# CO2-Ampel-Pro_v12.net
KiCad netlist of a schematic drawn in EAGLE
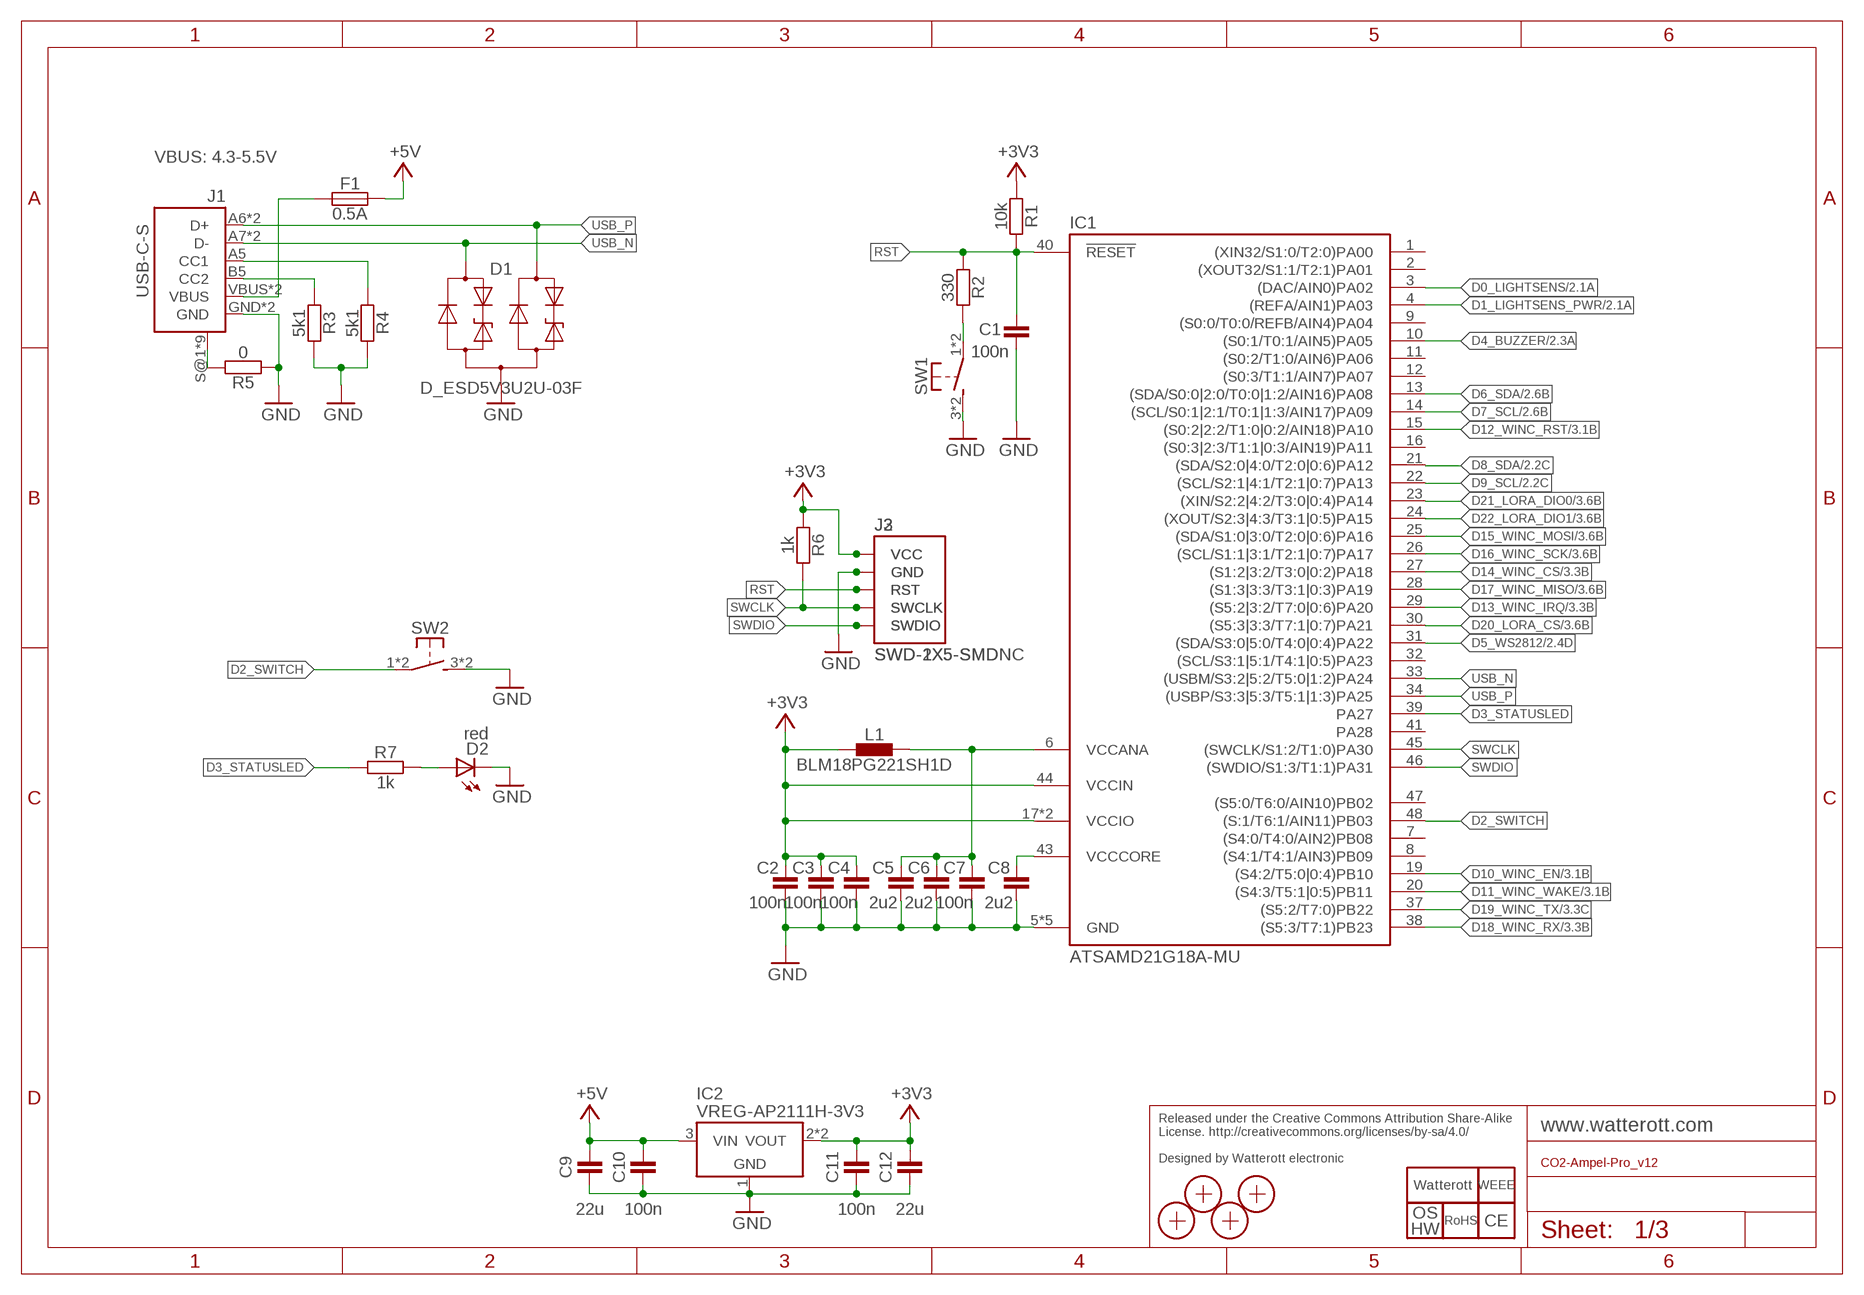
[diagram p0: schematic, sheet 1]
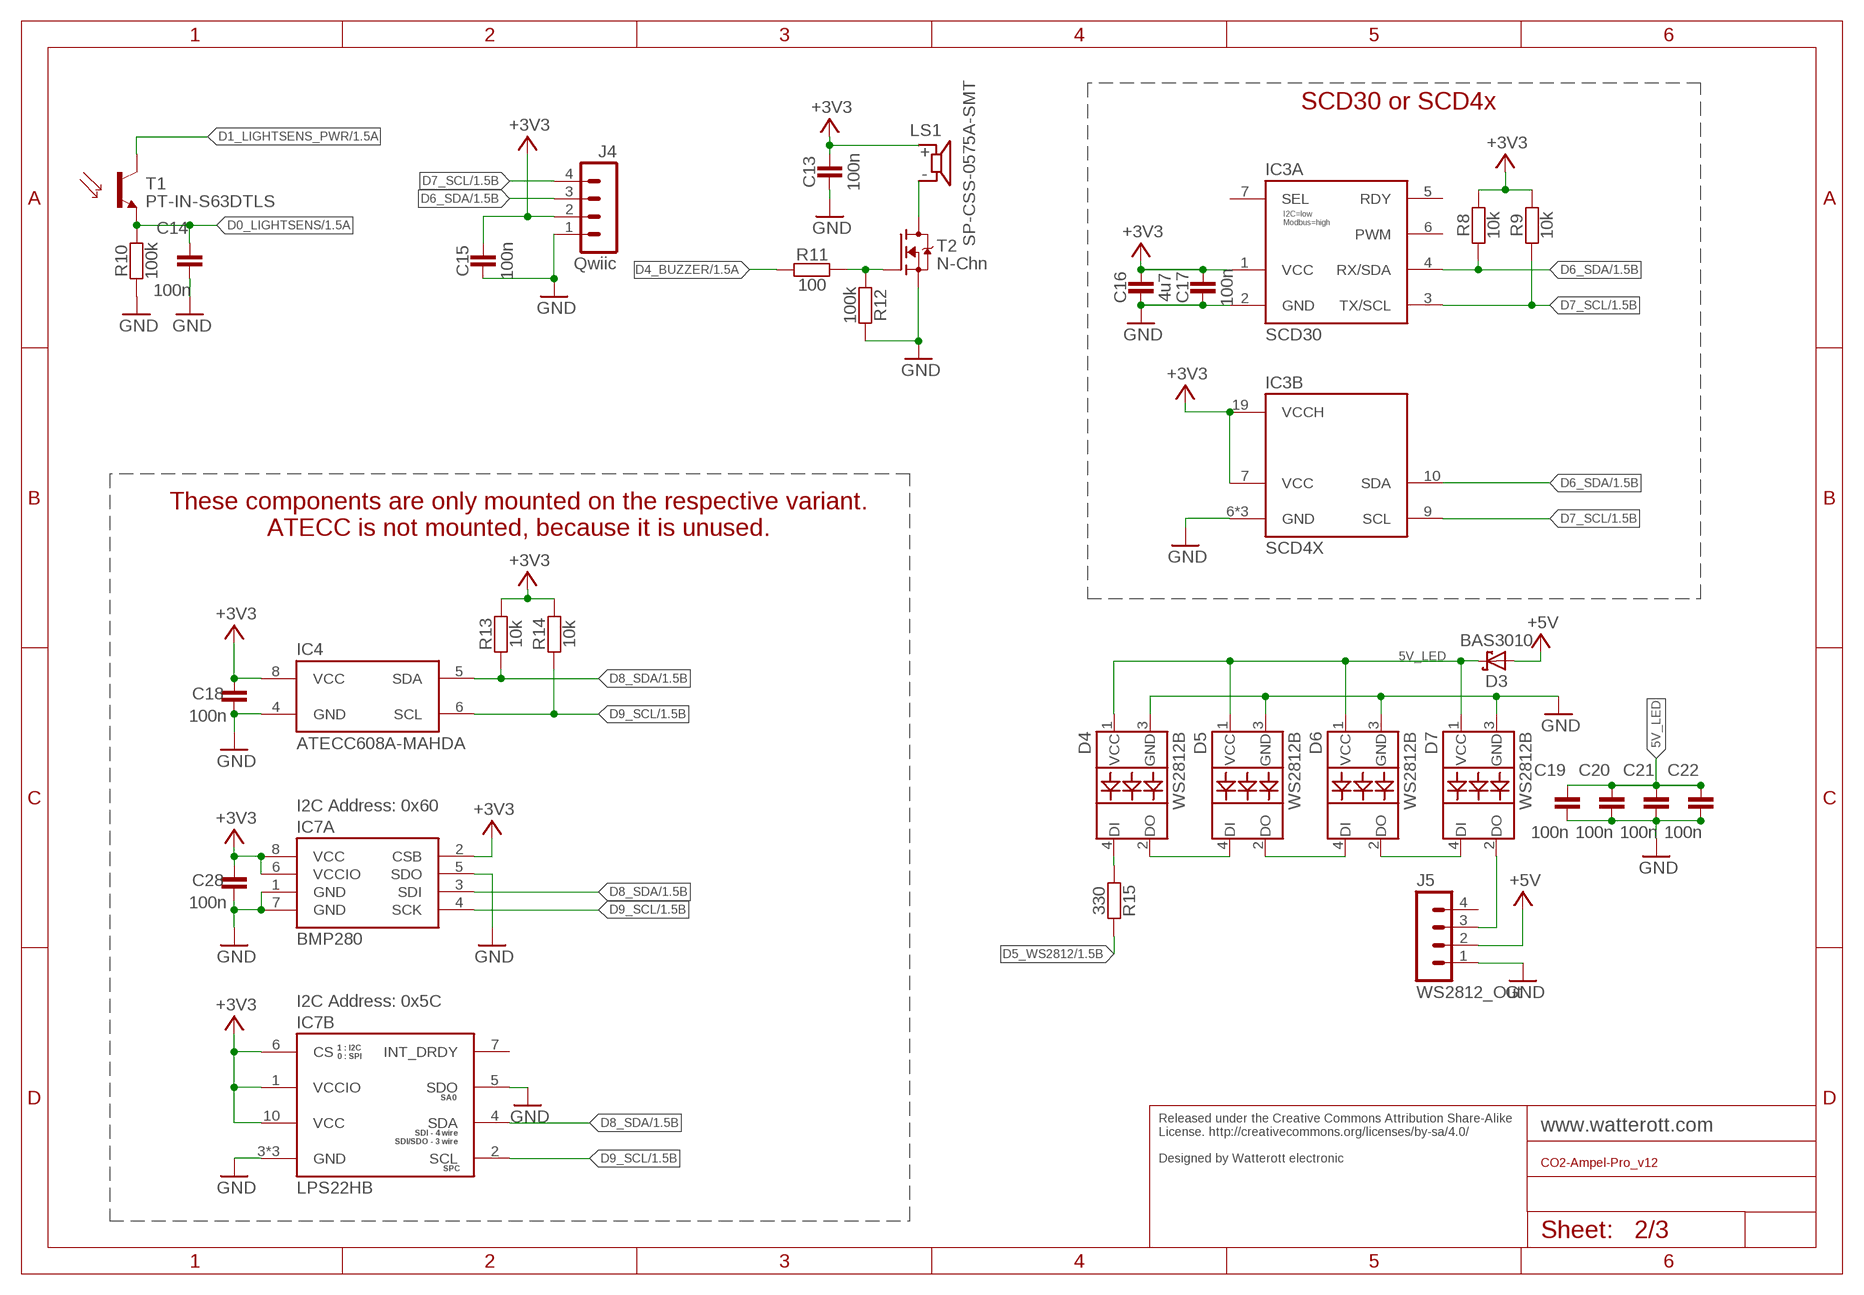
[diagram p1: schematic, sheet 2]
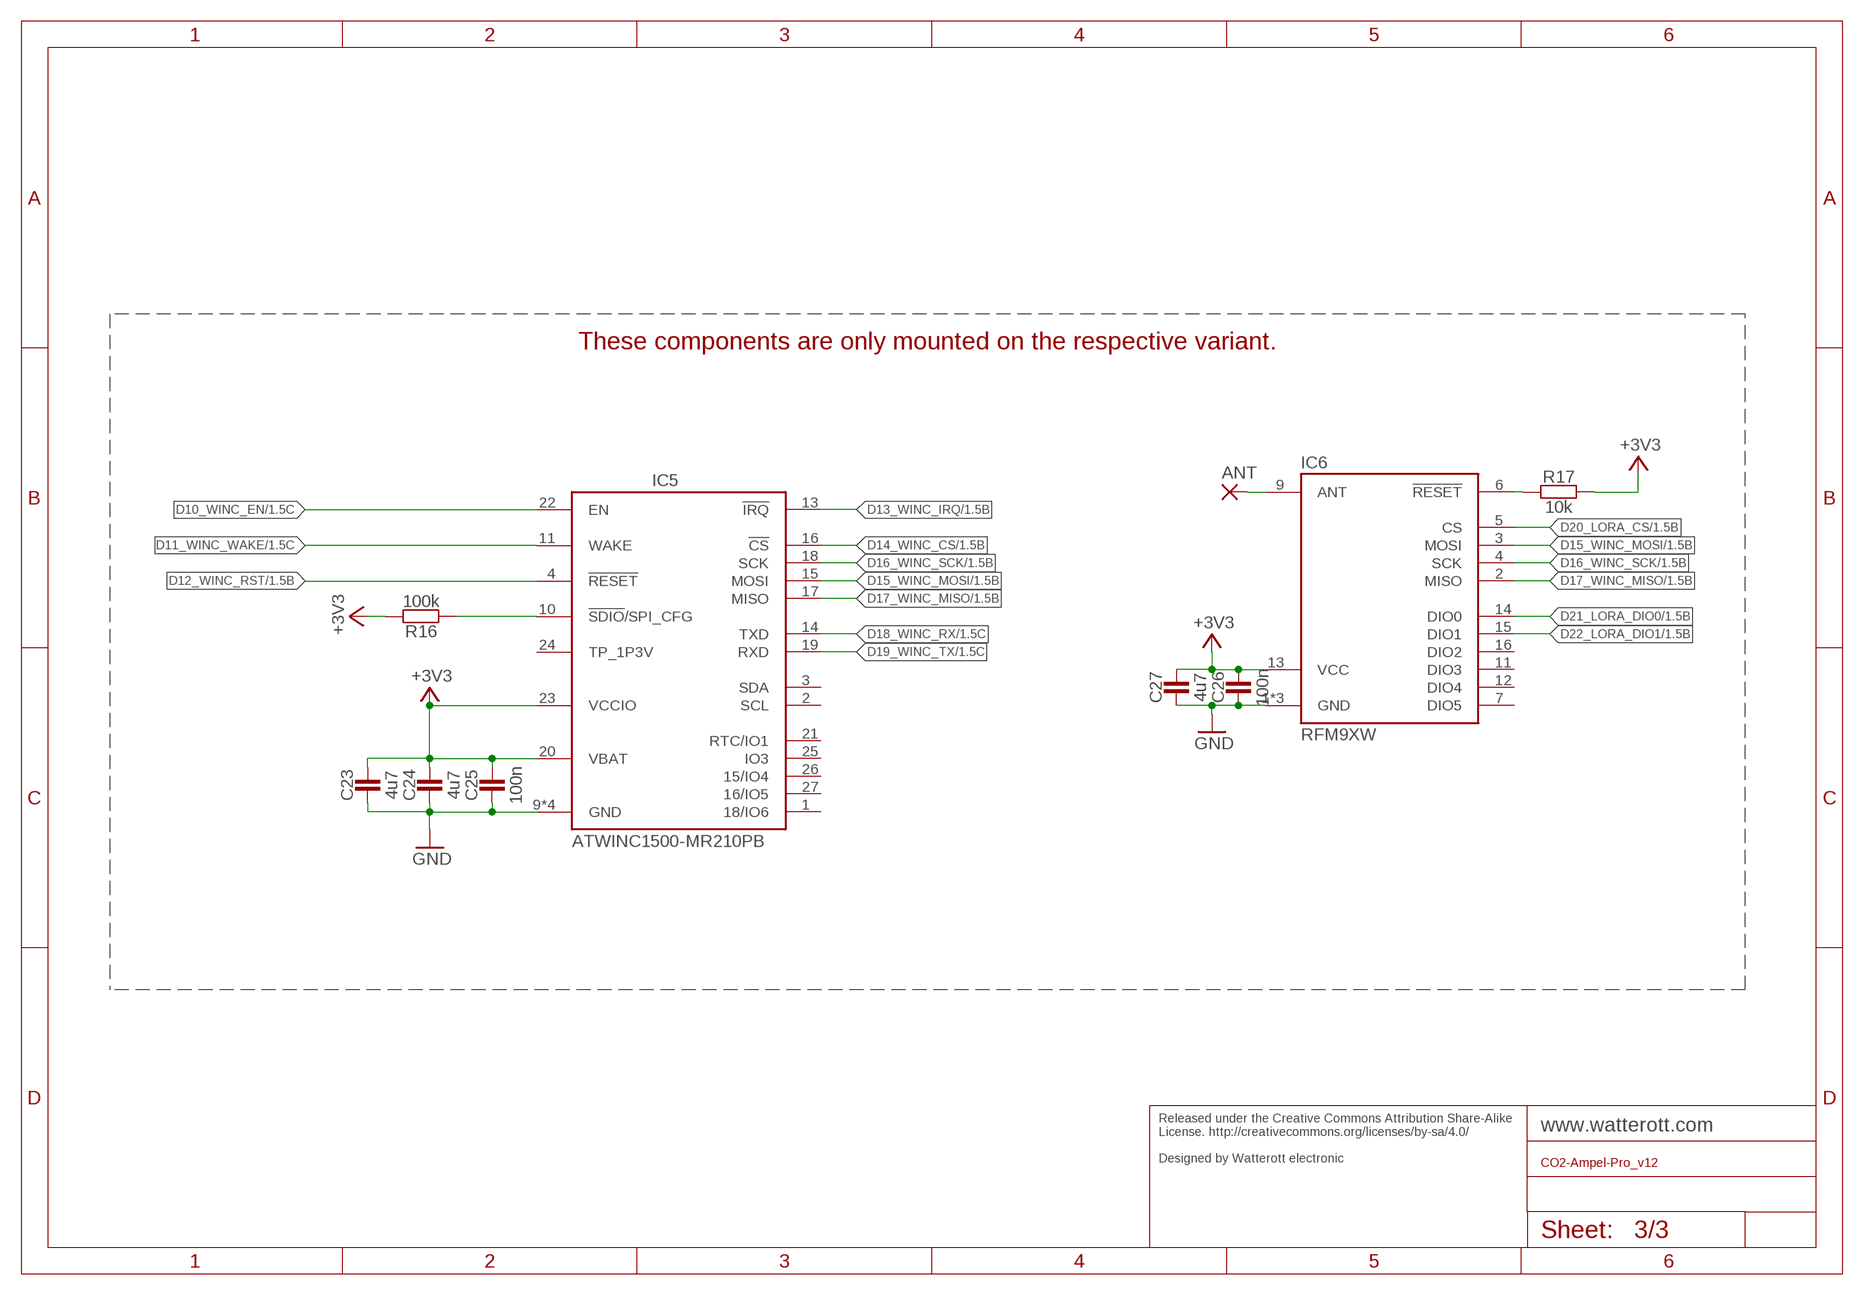
[diagram p2: schematic, sheet 3]

(export (version "E")
  (design (tool "Eeschema 10.0.6"))
  (components
    (comp (ref "C13")
      (value "100n")
      (footprint "eagle-import:C0402")
      (libsource (lib "eagle-import") (part "CAPACITOR-0402"))
    )
    (comp (ref "C14")
      (value "100n")
      (footprint "eagle-import:C0402")
      (libsource (lib "eagle-import") (part "CAPACITOR-0402"))
    )
    (comp (ref "C15")
      (value "100n")
      (footprint "eagle-import:C0402")
      (libsource (lib "eagle-import") (part "CAPACITOR-0402"))
    )
    (comp (ref "C16")
      (value "4u7")
      (footprint "eagle-import:C0402")
      (libsource (lib "eagle-import") (part "CAPACITOR-0402"))
    )
    (comp (ref "C17")
      (value "100n")
      (footprint "eagle-import:C0402")
      (libsource (lib "eagle-import") (part "CAPACITOR-0402"))
    )
    (comp (ref "C18")
      (value "100n")
      (footprint "eagle-import:C0402")
      (libsource (lib "eagle-import") (part "CAPACITOR-0402"))
    )
    (comp (ref "C19")
      (value "100n")
      (footprint "eagle-import:C0402")
      (libsource (lib "eagle-import") (part "CAPACITOR-0402"))
    )
    (comp (ref "C20")
      (value "100n")
      (footprint "eagle-import:C0402")
      (libsource (lib "eagle-import") (part "CAPACITOR-0402"))
    )
    (comp (ref "C21")
      (value "100n")
      (footprint "eagle-import:C0402")
      (libsource (lib "eagle-import") (part "CAPACITOR-0402"))
    )
    (comp (ref "C22")
      (value "100n")
      (footprint "eagle-import:C0402")
      (libsource (lib "eagle-import") (part "CAPACITOR-0402"))
    )
    (comp (ref "C28")
      (value "100n")
      (footprint "eagle-import:C0402")
      (libsource (lib "eagle-import") (part "CAPACITOR-0402"))
    )
    (comp (ref "D3")
      (value "BAS3010")
      (footprint "eagle-import:SOD323")
      (libsource (lib "eagle-import") (part "D_SCHOTTKY-SOD323"))
    )
    (comp (ref "D4")
      (value "WS2812B")
      (footprint "eagle-import:WS2812B")
      (libsource (lib "eagle-import") (part "WS2812B"))
    )
    (comp (ref "D5")
      (value "WS2812B")
      (footprint "eagle-import:WS2812B")
      (libsource (lib "eagle-import") (part "WS2812B"))
    )
    (comp (ref "D6")
      (value "WS2812B")
      (footprint "eagle-import:WS2812B")
      (libsource (lib "eagle-import") (part "WS2812B"))
    )
    (comp (ref "D7")
      (value "WS2812B")
      (footprint "eagle-import:WS2812B")
      (libsource (lib "eagle-import") (part "WS2812B"))
    )
    (comp (ref "IC3A")
      (value "SCD30")
      (footprint "eagle-import:SCD30")
      (libsource (lib "eagle-import") (part "SCD30"))
    )
    (comp (ref "IC3B")
      (value "SCD4X")
      (footprint "eagle-import:SCD4X")
      (libsource (lib "eagle-import") (part "SCD4X"))
    )
    (comp (ref "IC4")
      (value "ATECC608A-MAHDA")
      (footprint "eagle-import:UDFN8")
      (libsource (lib "eagle-import") (part "ATECC608A-MAHDA"))
    )
    (comp (ref "IC7A")
      (value "BMP280")
      (footprint "eagle-import:LGA8")
      (libsource (lib "eagle-import") (part "BMP280"))
    )
    (comp (ref "IC7B")
      (value "LPS22HB")
      (footprint "eagle-import:LPS22HB")
      (libsource (lib "eagle-import") (part "LPS22HB"))
    )
    (comp (ref "J4")
      (value "Qwiic")
      (footprint "eagle-import:JST_SM04B-SRSS-TB")
      (libsource (lib "eagle-import") (part "JST4-SM04B-SRSS-TB"))
    )
    (comp (ref "J5")
      (value "WS2812_Out")
      (footprint "eagle-import:JST_SM04B-SRSS-TB")
      (libsource (lib "eagle-import") (part "JST4-SM04B-SRSS-TB"))
    )
    (comp (ref "LS1")
      (value "SP-CSS-0575A-SMT")
      (footprint "eagle-import:CUI_CSS-0575A-SMT")
      (fields (field (name "MF") "CUI") (field (name "MPN") "CSS-0575A-SMT"))
      (libsource (lib "eagle-import") (part "SP-CSS-0575A-SMT"))
    )
    (comp (ref "R8")
      (value "10k")
      (footprint "eagle-import:C0402")
      (libsource (lib "eagle-import") (part "RESISTOR-0402"))
    )
    (comp (ref "R9")
      (value "10k")
      (footprint "eagle-import:C0402")
      (libsource (lib "eagle-import") (part "RESISTOR-0402"))
    )
    (comp (ref "R10")
      (value "100k")
      (footprint "eagle-import:C0402")
      (libsource (lib "eagle-import") (part "RESISTOR-0402"))
    )
    (comp (ref "R11")
      (value "100")
      (footprint "eagle-import:C0402")
      (libsource (lib "eagle-import") (part "RESISTOR-0402"))
    )
    (comp (ref "R12")
      (value "100k")
      (footprint "eagle-import:C0402")
      (libsource (lib "eagle-import") (part "RESISTOR-0402"))
    )
    (comp (ref "R13")
      (value "10k")
      (footprint "eagle-import:C0402")
      (libsource (lib "eagle-import") (part "RESISTOR-0402"))
    )
    (comp (ref "R14")
      (value "10k")
      (footprint "eagle-import:C0402")
      (libsource (lib "eagle-import") (part "RESISTOR-0402"))
    )
    (comp (ref "R15")
      (value "330")
      (footprint "eagle-import:C0402")
      (libsource (lib "eagle-import") (part "RESISTOR-0402"))
    )
    (comp (ref "T1")
      (value "PT-IN-S63DTLS")
      (footprint "eagle-import:C0603T")
      (libsource (lib "eagle-import") (part "PT-IN-S63DTLS"))
    )
    (comp (ref "T2")
      (value "N-Chn")
      (footprint "eagle-import:SOT23")
      (libsource (lib "eagle-import") (part "MOSFET-N-SOT23"))
    )
    (comp (ref "C1")
      (value "100n")
      (footprint "eagle-import:C0402")
      (libsource (lib "eagle-import") (part "CAPACITOR-0402"))
    )
    (comp (ref "C2")
      (value "100n")
      (footprint "eagle-import:C0402")
      (libsource (lib "eagle-import") (part "CAPACITOR-0402"))
    )
    (comp (ref "C3")
      (value "100n")
      (footprint "eagle-import:C0402")
      (libsource (lib "eagle-import") (part "CAPACITOR-0402"))
    )
    (comp (ref "C4")
      (value "100n")
      (footprint "eagle-import:C0402")
      (libsource (lib "eagle-import") (part "CAPACITOR-0402"))
    )
    (comp (ref "C5")
      (value "2u2")
      (footprint "eagle-import:C0402")
      (libsource (lib "eagle-import") (part "CAPACITOR-0402"))
    )
    (comp (ref "C6")
      (value "2u2")
      (footprint "eagle-import:C0402")
      (libsource (lib "eagle-import") (part "CAPACITOR-0402"))
    )
    (comp (ref "C7")
      (value "100n")
      (footprint "eagle-import:C0402")
      (libsource (lib "eagle-import") (part "CAPACITOR-0402"))
    )
    (comp (ref "C8")
      (value "2u2")
      (footprint "eagle-import:C0402")
      (libsource (lib "eagle-import") (part "CAPACITOR-0402"))
    )
    (comp (ref "C9")
      (value "22u")
      (footprint "eagle-import:C0805")
      (libsource (lib "eagle-import") (part "CAPACITOR-0805"))
    )
    (comp (ref "C10")
      (value "100n")
      (footprint "eagle-import:C0402")
      (libsource (lib "eagle-import") (part "CAPACITOR-0402"))
    )
    (comp (ref "C11")
      (value "100n")
      (footprint "eagle-import:C0402")
      (libsource (lib "eagle-import") (part "CAPACITOR-0402"))
    )
    (comp (ref "C12")
      (value "22u")
      (footprint "eagle-import:C0805")
      (libsource (lib "eagle-import") (part "CAPACITOR-0805"))
    )
    (comp (ref "D1")
      (value "D_ESD5V3U2U-03F")
      (footprint "eagle-import:SOT723")
      (libsource (lib "eagle-import") (part "D_ESD5V3U2U-03F"))
    )
    (comp (ref "D2")
      (value "red")
      (footprint "eagle-import:C0603")
      (libsource (lib "eagle-import") (part "LED-0603"))
    )
    (comp (ref "F1")
      (value "0.5A")
      (footprint "eagle-import:C0805")
      (libsource (lib "eagle-import") (part "FUSE-0805"))
    )
    (comp (ref "IC1")
      (value "ATSAMD21G18A-MU")
      (footprint "eagle-import:QFN48-PAD")
      (libsource (lib "eagle-import") (part "ATSAMD21G18A-MU"))
    )
    (comp (ref "IC2")
      (value "VREG-AP2111H-3V3")
      (footprint "eagle-import:SOT223")
      (libsource (lib "eagle-import") (part "VREG-TS1117CW-3V3"))
    )
    (comp (ref "J1")
      (value "USB-C-S")
      (footprint "eagle-import:USB-C-S")
      (libsource (lib "eagle-import") (part "USB-C-S"))
    )
    (comp (ref "J2")
      (value "SWD-2X5-SMD")
      (footprint "eagle-import:SWD-2X5_SMD")
      (libsource (lib "eagle-import") (part "SWD-2X5-SMD"))
    )
    (comp (ref "J3")
      (value "SWD-1X5-SMDNC")
      (footprint "eagle-import:SWD-1X5_SMDNC")
      (libsource (lib "eagle-import") (part "SWD-1X5-SMDNC"))
    )
    (comp (ref "L1")
      (value "BLM18PG221SH1D")
      (footprint "eagle-import:C0603")
      (libsource (lib "eagle-import") (part "INDUCTOR-0603"))
    )
    (comp (ref "LOGO1")
      (value "LOGO_SPARK-4")
      (footprint "eagle-import:SPARK_4MM")
      (libsource (lib "eagle-import") (part "LOGO_SPARK-4"))
    )
    (comp (ref "LOGO2")
      (value "LOGO_WEEE-4")
      (footprint "eagle-import:WEEE_4MM")
      (libsource (lib "eagle-import") (part "LOGO_WEEE-4"))
    )
    (comp (ref "LOGO3")
      (value "OSHW_LOGOX0070")
      (footprint "eagle-import:OSHW_3MM")
      (libsource (lib "eagle-import") (part "LOGO_OSHW-3"))
    )
    (comp (ref "LOGO4")
      (value "LOGO_ROHS-4")
      (footprint "eagle-import:ROHS_4MM")
      (libsource (lib "eagle-import") (part "LOGO_ROHS-4"))
    )
    (comp (ref "LOGO5")
      (value "LOGO_CE-4")
      (footprint "eagle-import:CE_4MM")
      (libsource (lib "eagle-import") (part "LOGO_CE-4"))
    )
    (comp (ref "R1")
      (value "10k")
      (footprint "eagle-import:C0402")
      (libsource (lib "eagle-import") (part "RESISTOR-0402"))
    )
    (comp (ref "R2")
      (value "330")
      (footprint "eagle-import:C0402")
      (libsource (lib "eagle-import") (part "RESISTOR-0402"))
    )
    (comp (ref "R3")
      (value "5k1")
      (footprint "eagle-import:C0402")
      (libsource (lib "eagle-import") (part "RESISTOR-0402"))
    )
    (comp (ref "R4")
      (value "5k1")
      (footprint "eagle-import:C0402")
      (libsource (lib "eagle-import") (part "RESISTOR-0402"))
    )
    (comp (ref "R5")
      (value "0")
      (footprint "eagle-import:C0603")
      (libsource (lib "eagle-import") (part "RESISTOR-0603"))
    )
    (comp (ref "R6")
      (value "1k")
      (footprint "eagle-import:C0402")
      (libsource (lib "eagle-import") (part "RESISTOR-0402"))
    )
    (comp (ref "R7")
      (value "1k")
      (footprint "eagle-import:C0402")
      (libsource (lib "eagle-import") (part "RESISTOR-0402"))
    )
    (comp (ref "SW1")
      (value "PTS645SK50SMTR92-Red")
      (footprint "eagle-import:PTS840P")
      (libsource (lib "eagle-import") (part "SW-TACTILE-PTS840P"))
    )
    (comp (ref "SW2")
      (value "PTS645SH50SMTR92-Grey")
      (footprint "eagle-import:PTS840P")
      (libsource (lib "eagle-import") (part "SW-TACTILE-PTS840P"))
    )
    (comp (ref "X1")
      (value "PASSER-07")
      (footprint "eagle-import:PASSER_07MM")
      (libsource (lib "eagle-import") (part "PASSER-07"))
    )
    (comp (ref "X2")
      (value "PASSER-07")
      (footprint "eagle-import:PASSER_07MM")
      (libsource (lib "eagle-import") (part "PASSER-07"))
    )
    (comp (ref "X3")
      (value "PASSER-07")
      (footprint "eagle-import:PASSER_07MM")
      (libsource (lib "eagle-import") (part "PASSER-07"))
    )
    (comp (ref "X4")
      (value "PASSER-07")
      (footprint "eagle-import:PASSER_07MM")
      (libsource (lib "eagle-import") (part "PASSER-07"))
    )
    (comp (ref "ANT")
      (value "1,6/0,9")
      (footprint "eagle-import:1,6_0,9")
      (libsource (lib "eagle-import") (part "1,6/0,9"))
    )
    (comp (ref "C23")
      (value "4u7")
      (footprint "eagle-import:C0402")
      (libsource (lib "eagle-import") (part "CAPACITOR-0402"))
    )
    (comp (ref "C24")
      (value "4u7")
      (footprint "eagle-import:C0402")
      (libsource (lib "eagle-import") (part "CAPACITOR-0402"))
    )
    (comp (ref "C25")
      (value "100n")
      (footprint "eagle-import:C0402")
      (libsource (lib "eagle-import") (part "CAPACITOR-0402"))
    )
    (comp (ref "C26")
      (value "100n")
      (footprint "eagle-import:C0402")
      (libsource (lib "eagle-import") (part "CAPACITOR-0402"))
    )
    (comp (ref "C27")
      (value "4u7")
      (footprint "eagle-import:C0402")
      (libsource (lib "eagle-import") (part "CAPACITOR-0402"))
    )
    (comp (ref "IC5")
      (value "ATWINC1500-MR210PB")
      (footprint "eagle-import:ATWINC1500-MX210")
      (libsource (lib "eagle-import") (part "ATWINC1500-MR210PB"))
    )
    (comp (ref "IC6")
      (value "RFM9XW")
      (footprint "eagle-import:RFM9X")
      (libsource (lib "eagle-import") (part "RFM9XW"))
    )
    (comp (ref "R16")
      (value "100k")
      (footprint "eagle-import:C0402")
      (libsource (lib "eagle-import") (part "RESISTOR-0402"))
    )
    (comp (ref "R17")
      (value "10k")
      (footprint "eagle-import:C0402")
      (libsource (lib "eagle-import") (part "RESISTOR-0402"))
    )
  )
  (nets
    (net (code "1") (name "+3V3") (class "Default")
      (node (ref "C11") (pin "2") (pinfunction "2_2") (pintype "passive"))
      (node (ref "C12") (pin "2") (pinfunction "2_2") (pintype "passive"))
      (node (ref "C13") (pin "2") (pinfunction "2_2") (pintype "passive"))
      (node (ref "C15") (pin "2") (pinfunction "2_2") (pintype "passive"))
      (node (ref "C16") (pin "2") (pinfunction "2_2") (pintype "passive"))
      (node (ref "C17") (pin "2") (pinfunction "2_2") (pintype "passive"))
      (node (ref "C18") (pin "2") (pinfunction "2_2") (pintype "passive"))
      (node (ref "C2") (pin "2") (pinfunction "2_2") (pintype "passive"))
      (node (ref "C23") (pin "2") (pinfunction "2_2") (pintype "passive"))
      (node (ref "C24") (pin "2") (pinfunction "2_2") (pintype "passive"))
      (node (ref "C25") (pin "2") (pinfunction "2_2") (pintype "passive"))
      (node (ref "C26") (pin "2") (pinfunction "2_2") (pintype "passive"))
      (node (ref "C27") (pin "2") (pinfunction "2_2") (pintype "passive"))
      (node (ref "C28") (pin "2") (pinfunction "2_2") (pintype "passive"))
      (node (ref "C3") (pin "2") (pinfunction "2_2") (pintype "passive"))
      (node (ref "C4") (pin "2") (pinfunction "2_2") (pintype "passive"))
      (node (ref "IC1") (pin "17") (pinfunction "VCCIO_17") (pintype "power_in"))
      (node (ref "IC1") (pin "36") (pinfunction "VCCIO_36") (pintype "power_in"))
      (node (ref "IC1") (pin "44") (pinfunction "VCCIN_44") (pintype "power_in"))
      (node (ref "IC2") (pin "2") (pinfunction "VOUT_2") (pintype "power_in"))
      (node (ref "IC2") (pin "4") (pinfunction "VOUT_4") (pintype "power_in"))
      (node (ref "IC3A") (pin "1") (pinfunction "VCC_1") (pintype "power_in"))
      (node (ref "IC3B") (pin "19") (pinfunction "VCCH_19") (pintype "bidirectional"))
      (node (ref "IC3B") (pin "7") (pinfunction "VCC_7") (pintype "power_in"))
      (node (ref "IC4") (pin "8") (pinfunction "VCC_8") (pintype "power_in"))
      (node (ref "IC5") (pin "20") (pinfunction "VBAT_20") (pintype "power_in"))
      (node (ref "IC5") (pin "23") (pinfunction "VCCIO_23") (pintype "power_in"))
      (node (ref "IC6") (pin "13") (pinfunction "VCC_13") (pintype "power_in"))
      (node (ref "IC7A") (pin "2") (pinfunction "CSB_2") (pintype "input"))
      (node (ref "IC7A") (pin "6") (pinfunction "VCCIO_6") (pintype "power_in"))
      (node (ref "IC7A") (pin "8") (pinfunction "VCC_8") (pintype "power_in"))
      (node (ref "IC7B") (pin "1") (pinfunction "VCCIO_1") (pintype "bidirectional"))
      (node (ref "IC7B") (pin "10") (pinfunction "VCC_10") (pintype "power_in"))
      (node (ref "IC7B") (pin "6") (pinfunction "CS_6") (pintype "bidirectional"))
      (node (ref "J2") (pin "VCC") (pinfunction "VCC_VCC") (pintype "power_in"))
      (node (ref "J3") (pin "1-VCC") (pinfunction "VCC_1-VCC") (pintype "power_in"))
      (node (ref "J4") (pin "2") (pinfunction "2_2") (pintype "passive"))
      (node (ref "L1") (pin "1") (pinfunction "1_1") (pintype "passive"))
      (node (ref "LS1") (pin "+") (pinfunction "P_+") (pintype "passive"))
      (node (ref "R1") (pin "1") (pinfunction "1_1") (pintype "passive"))
      (node (ref "R13") (pin "2") (pinfunction "2_2") (pintype "passive"))
      (node (ref "R14") (pin "2") (pinfunction "2_2") (pintype "passive"))
      (node (ref "R16") (pin "2") (pinfunction "2_2") (pintype "passive"))
      (node (ref "R17") (pin "2") (pinfunction "2_2") (pintype "passive"))
      (node (ref "R6") (pin "1") (pinfunction "1_1") (pintype "passive"))
      (node (ref "R8") (pin "2") (pinfunction "2_2") (pintype "passive"))
      (node (ref "R9") (pin "2") (pinfunction "2_2") (pintype "passive"))
    )
    (net (code "2") (name "+5V") (class "Default")
      (node (ref "C10") (pin "2") (pinfunction "2_2") (pintype "passive"))
      (node (ref "C9") (pin "2") (pinfunction "2_2") (pintype "passive"))
      (node (ref "D3") (pin "A") (pinfunction "A_A") (pintype "passive"))
      (node (ref "F1") (pin "2") (pinfunction "2_2") (pintype "passive"))
      (node (ref "IC2") (pin "3") (pinfunction "VIN_3") (pintype "power_in"))
      (node (ref "J5") (pin "2") (pinfunction "2_2") (pintype "passive"))
    )
    (net (code "3") (name "5V_LED") (class "Default")
      (node (ref "C19") (pin "2") (pinfunction "2_2") (pintype "passive"))
      (node (ref "C20") (pin "2") (pinfunction "2_2") (pintype "passive"))
      (node (ref "C21") (pin "2") (pinfunction "2_2") (pintype "passive"))
      (node (ref "C22") (pin "2") (pinfunction "2_2") (pintype "passive"))
      (node (ref "D3") (pin "C") (pinfunction "C_C") (pintype "passive"))
      (node (ref "D4") (pin "1") (pinfunction "VCC_1") (pintype "power_in"))
      (node (ref "D5") (pin "1") (pinfunction "VCC_1") (pintype "power_in"))
      (node (ref "D6") (pin "1") (pinfunction "VCC_1") (pintype "power_in"))
      (node (ref "D7") (pin "1") (pinfunction "VCC_1") (pintype "power_in"))
    )
    (net (code "4") (name "D0_LIGHTSENS") (class "Default")
      (node (ref "C14") (pin "2") (pinfunction "2_2") (pintype "passive"))
      (node (ref "IC1") (pin "3") (pinfunction "(DAC/AIN0)PA02_3") (pintype "bidirectional"))
      (node (ref "R10") (pin "2") (pinfunction "2_2") (pintype "passive"))
      (node (ref "T1") (pin "E") (pinfunction "E_E") (pintype "passive"))
    )
    (net (code "5") (name "D1_LIGHTSENS_PWR") (class "Default")
      (node (ref "IC1") (pin "4") (pinfunction "(REFA/AIN1)PA03_4") (pintype "bidirectional"))
      (node (ref "T1") (pin "C") (pinfunction "C_C") (pintype "passive"))
    )
    (net (code "6") (name "D2_SWITCH") (class "Default")
      (node (ref "IC1") (pin "48") (pinfunction "(S:1/T6:1/AIN11)PB03_48") (pintype "bidirectional"))
      (node (ref "SW2") (pin "1") (pinfunction "P1_1") (pintype "passive"))
      (node (ref "SW2") (pin "2") (pinfunction "P1_2") (pintype "passive"))
    )
    (net (code "7") (name "D3_STATUSLED") (class "Default")
      (node (ref "IC1") (pin "39") (pinfunction "PA27_39") (pintype "bidirectional"))
      (node (ref "R7") (pin "1") (pinfunction "1_1") (pintype "passive"))
    )
    (net (code "8") (name "D4_BUZZER") (class "Default")
      (node (ref "IC1") (pin "10") (pinfunction "(S0:1/T0:1/AIN5)PA05_10") (pintype "bidirectional"))
      (node (ref "R11") (pin "1") (pinfunction "1_1") (pintype "passive"))
    )
    (net (code "9") (name "D5_WS2812") (class "Default")
      (node (ref "IC1") (pin "31") (pinfunction "(SDA/S3:0|5:0/T4:0|0:4)PA22_31") (pintype "bidirectional"))
      (node (ref "R15") (pin "2") (pinfunction "2_2") (pintype "passive"))
    )
    (net (code "10") (name "D6_SDA") (class "Default")
      (node (ref "IC1") (pin "13") (pinfunction "(SDA/S0:0|2:0/T0:0|1:2/AIN16)PA08_13") (pintype "bidirectional"))
      (node (ref "IC3A") (pin "4") (pinfunction "RX/SDA_4") (pintype "bidirectional"))
      (node (ref "IC3B") (pin "10") (pinfunction "SDA_10") (pintype "bidirectional"))
      (node (ref "J4") (pin "3") (pinfunction "3_3") (pintype "passive"))
      (node (ref "R8") (pin "1") (pinfunction "1_1") (pintype "passive"))
    )
    (net (code "11") (name "D7_SCL") (class "Default")
      (node (ref "IC1") (pin "14") (pinfunction "(SCL/S0:1|2:1/T0:1|1:3/AIN17)PA09_14") (pintype "bidirectional"))
      (node (ref "IC3A") (pin "3") (pinfunction "TX/SCL_3") (pintype "bidirectional"))
      (node (ref "IC3B") (pin "9") (pinfunction "SCL_9") (pintype "bidirectional"))
      (node (ref "J4") (pin "4") (pinfunction "4_4") (pintype "passive"))
      (node (ref "R9") (pin "1") (pinfunction "1_1") (pintype "passive"))
    )
    (net (code "12") (name "D8_SDA") (class "Default")
      (node (ref "IC1") (pin "21") (pinfunction "(SDA/S2:0|4:0/T2:0|0:6)PA12_21") (pintype "bidirectional"))
      (node (ref "IC4") (pin "5") (pinfunction "SDA_5") (pintype "bidirectional"))
      (node (ref "IC7A") (pin "3") (pinfunction "SDI_3") (pintype "bidirectional"))
      (node (ref "IC7B") (pin "4") (pinfunction "SDA_4") (pintype "bidirectional"))
      (node (ref "R13") (pin "1") (pinfunction "1_1") (pintype "passive"))
    )
    (net (code "13") (name "D9_SCL") (class "Default")
      (node (ref "IC1") (pin "22") (pinfunction "(SCL/S2:1|4:1/T2:1|0:7)PA13_22") (pintype "bidirectional"))
      (node (ref "IC4") (pin "6") (pinfunction "SCL_6") (pintype "bidirectional"))
      (node (ref "IC7A") (pin "4") (pinfunction "SCK_4") (pintype "bidirectional"))
      (node (ref "IC7B") (pin "2") (pinfunction "SCL_2") (pintype "bidirectional"))
      (node (ref "R14") (pin "1") (pinfunction "1_1") (pintype "passive"))
    )
    (net (code "14") (name "D10_WINC_EN") (class "Default")
      (node (ref "IC1") (pin "19") (pinfunction "(S4:2/T5:0|0:4)PB10_19") (pintype "bidirectional"))
      (node (ref "IC5") (pin "22") (pinfunction "EN_22") (pintype "input"))
    )
    (net (code "15") (name "D11_WINC_WAKE") (class "Default")
      (node (ref "IC1") (pin "20") (pinfunction "(S4:3/T5:1|0:5)PB11_20") (pintype "bidirectional"))
      (node (ref "IC5") (pin "11") (pinfunction "WAKE_11") (pintype "input"))
    )
    (net (code "16") (name "D12_WINC_RST") (class "Default")
      (node (ref "IC1") (pin "15") (pinfunction "(S0:2|2:2/T1:0|0:2/AIN18)PA10_15") (pintype "bidirectional"))
      (node (ref "IC5") (pin "4") (pinfunction "~{RESET}_4") (pintype "input"))
    )
    (net (code "17") (name "D13_WINC_IRQ") (class "Default")
      (node (ref "IC1") (pin "29") (pinfunction "(S5:2|3:2/T7:0|0:6)PA20_29") (pintype "bidirectional"))
      (node (ref "IC5") (pin "13") (pinfunction "~{IRQ}_13") (pintype "output"))
    )
    (net (code "18") (name "D14_WINC_CS") (class "Default")
      (node (ref "IC1") (pin "27") (pinfunction "(S1:2|3:2/T3:0|0:2)PA18_27") (pintype "bidirectional"))
      (node (ref "IC5") (pin "16") (pinfunction "~{CS}_16") (pintype "input"))
    )
    (net (code "19") (name "D15_WINC_MOSI") (class "Default")
      (node (ref "IC1") (pin "25") (pinfunction "(SDA/S1:0|3:0/T2:0|0:6)PA16_25") (pintype "bidirectional"))
      (node (ref "IC5") (pin "15") (pinfunction "MOSI_15") (pintype "input"))
      (node (ref "IC6") (pin "3") (pinfunction "MOSI_3") (pintype "input"))
    )
    (net (code "20") (name "D16_WINC_SCK") (class "Default")
      (node (ref "IC1") (pin "26") (pinfunction "(SCL/S1:1|3:1/T2:1|0:7)PA17_26") (pintype "bidirectional"))
      (node (ref "IC5") (pin "18") (pinfunction "SCK_18") (pintype "input"))
      (node (ref "IC6") (pin "4") (pinfunction "SCK_4") (pintype "input"))
    )
    (net (code "21") (name "D17_WINC_MISO") (class "Default")
      (node (ref "IC1") (pin "28") (pinfunction "(S1:3|3:3/T3:1|0:3)PA19_28") (pintype "bidirectional"))
      (node (ref "IC5") (pin "17") (pinfunction "MISO_17") (pintype "output"))
      (node (ref "IC6") (pin "2") (pinfunction "MISO_2") (pintype "output"))
    )
    (net (code "22") (name "D18_WINC_RX") (class "Default")
      (node (ref "IC1") (pin "38") (pinfunction "(S5:3/T7:1)PB23_38") (pintype "bidirectional"))
      (node (ref "IC5") (pin "14") (pinfunction "TXD_14") (pintype "output"))
    )
    (net (code "23") (name "D19_WINC_TX") (class "Default")
      (node (ref "IC1") (pin "37") (pinfunction "(S5:2/T7:0)PB22_37") (pintype "bidirectional"))
      (node (ref "IC5") (pin "19") (pinfunction "RXD_19") (pintype "input"))
    )
    (net (code "24") (name "D20_LORA_CS") (class "Default")
      (node (ref "IC1") (pin "30") (pinfunction "(S5:3|3:3/T7:1|0:7)PA21_30") (pintype "bidirectional"))
      (node (ref "IC6") (pin "5") (pinfunction "CS_5") (pintype "input"))
    )
    (net (code "25") (name "D21_LORA_DIO0") (class "Default")
      (node (ref "IC1") (pin "23") (pinfunction "(XIN/S2:2|4:2/T3:0|0:4)PA14_23") (pintype "bidirectional"))
      (node (ref "IC6") (pin "14") (pinfunction "DIO0_14") (pintype "bidirectional"))
    )
    (net (code "26") (name "D22_LORA_DIO1") (class "Default")
      (node (ref "IC1") (pin "24") (pinfunction "(XOUT/S2:3|4:3/T3:1|0:5)PA15_24") (pintype "bidirectional"))
      (node (ref "IC6") (pin "15") (pinfunction "DIO1_15") (pintype "bidirectional"))
    )
    (net (code "27") (name "GND") (class "Default")
      (node (ref "C1") (pin "1") (pinfunction "1_1") (pintype "passive"))
      (node (ref "C10") (pin "1") (pinfunction "1_1") (pintype "passive"))
      (node (ref "C11") (pin "1") (pinfunction "1_1") (pintype "passive"))
      (node (ref "C12") (pin "1") (pinfunction "1_1") (pintype "passive"))
      (node (ref "C13") (pin "1") (pinfunction "1_1") (pintype "passive"))
      (node (ref "C14") (pin "1") (pinfunction "1_1") (pintype "passive"))
      (node (ref "C15") (pin "1") (pinfunction "1_1") (pintype "passive"))
      (node (ref "C16") (pin "1") (pinfunction "1_1") (pintype "passive"))
      (node (ref "C17") (pin "1") (pinfunction "1_1") (pintype "passive"))
      (node (ref "C18") (pin "1") (pinfunction "1_1") (pintype "passive"))
      (node (ref "C19") (pin "1") (pinfunction "1_1") (pintype "passive"))
      (node (ref "C2") (pin "1") (pinfunction "1_1") (pintype "passive"))
      (node (ref "C20") (pin "1") (pinfunction "1_1") (pintype "passive"))
      (node (ref "C21") (pin "1") (pinfunction "1_1") (pintype "passive"))
      (node (ref "C22") (pin "1") (pinfunction "1_1") (pintype "passive"))
      (node (ref "C23") (pin "1") (pinfunction "1_1") (pintype "passive"))
      (node (ref "C24") (pin "1") (pinfunction "1_1") (pintype "passive"))
      (node (ref "C25") (pin "1") (pinfunction "1_1") (pintype "passive"))
      (node (ref "C26") (pin "1") (pinfunction "1_1") (pintype "passive"))
      (node (ref "C27") (pin "1") (pinfunction "1_1") (pintype "passive"))
      (node (ref "C28") (pin "1") (pinfunction "1_1") (pintype "passive"))
      (node (ref "C3") (pin "1") (pinfunction "1_1") (pintype "passive"))
      (node (ref "C4") (pin "1") (pinfunction "1_1") (pintype "passive"))
      (node (ref "C5") (pin "1") (pinfunction "1_1") (pintype "passive"))
      (node (ref "C6") (pin "1") (pinfunction "1_1") (pintype "passive"))
      (node (ref "C7") (pin "1") (pinfunction "1_1") (pintype "passive"))
      (node (ref "C8") (pin "1") (pinfunction "1_1") (pintype "passive"))
      (node (ref "C9") (pin "1") (pinfunction "1_1") (pintype "passive"))
      (node (ref "D1") (pin "3") (pinfunction "A_3") (pintype "passive"))
      (node (ref "D2") (pin "C") (pinfunction "C_C") (pintype "passive"))
      (node (ref "D4") (pin "3") (pinfunction "GND_3") (pintype "power_in"))
      (node (ref "D5") (pin "3") (pinfunction "GND_3") (pintype "power_in"))
      (node (ref "D6") (pin "3") (pinfunction "GND_3") (pintype "power_in"))
      (node (ref "D7") (pin "3") (pinfunction "GND_3") (pintype "power_in"))
      (node (ref "IC1") (pin "18") (pinfunction "GND_18") (pintype "power_in"))
      (node (ref "IC1") (pin "35") (pinfunction "GND_35") (pintype "power_in"))
      (node (ref "IC1") (pin "42") (pinfunction "GND_42") (pintype "power_in"))
      (node (ref "IC1") (pin "5") (pinfunction "GND_5") (pintype "power_in"))
      (node (ref "IC1") (pin "TP") (pinfunction "GND_TP") (pintype "power_in"))
      (node (ref "IC2") (pin "1") (pinfunction "GND_1") (pintype "power_in"))
      (node (ref "IC3A") (pin "2") (pinfunction "GND_2") (pintype "power_in"))
      (node (ref "IC3B") (pin "20") (pinfunction "GND_20") (pintype "power_in"))
      (node (ref "IC3B") (pin "21") (pinfunction "GND_21") (pintype "power_in"))
      (node (ref "IC3B") (pin "6") (pinfunction "GND_6") (pintype "power_in"))
      (node (ref "IC4") (pin "4") (pinfunction "GND_4") (pintype "power_in"))
      (node (ref "IC5") (pin "12") (pinfunction "GND_12") (pintype "power_in"))
      (node (ref "IC5") (pin "28") (pinfunction "GND_28") (pintype "power_in"))
      (node (ref "IC5") (pin "9") (pinfunction "GND_9") (pintype "power_in"))
      (node (ref "IC5") (pin "GND") (pinfunction "GND_GND") (pintype "power_in"))
      (node (ref "IC6") (pin "1") (pinfunction "GND_1") (pintype "power_in"))
      (node (ref "IC6") (pin "10") (pinfunction "GND_10") (pintype "power_in"))
      (node (ref "IC6") (pin "8") (pinfunction "GND_8") (pintype "power_in"))
      (node (ref "IC7A") (pin "1") (pinfunction "GND_1") (pintype "power_in"))
      (node (ref "IC7A") (pin "5") (pinfunction "SDO_5") (pintype "bidirectional"))
      (node (ref "IC7A") (pin "7") (pinfunction "GND_7") (pintype "power_in"))
      (node (ref "IC7B") (pin "3") (pinfunction "GND_3") (pintype "power_in"))
      (node (ref "IC7B") (pin "5") (pinfunction "SDO_5") (pintype "bidirectional"))
      (node (ref "IC7B") (pin "8") (pinfunction "GND_8") (pintype "power_in"))
      (node (ref "IC7B") (pin "9") (pinfunction "GND_9") (pintype "power_in"))
      (node (ref "J1") (pin "GND") (pinfunction "GND_GND") (pintype "power_in"))
      (node (ref "J1") (pin "GND2") (pinfunction "GND_GND2") (pintype "power_in"))
      (node (ref "J2") (pin "GND@1") (pinfunction "GND_GND@1") (pintype "power_in"))
      (node (ref "J2") (pin "GND@2") (pinfunction "GND_GND@2") (pintype "power_in"))
      (node (ref "J2") (pin "GND@3") (pinfunction "GND_GND@3") (pintype "power_in"))
      (node (ref "J3") (pin "2-GND") (pinfunction "GND_2-GND") (pintype "power_in"))
      (node (ref "J4") (pin "1") (pinfunction "1_1") (pintype "passive"))
      (node (ref "J5") (pin "1") (pinfunction "1_1") (pintype "passive"))
      (node (ref "R10") (pin "1") (pinfunction "1_1") (pintype "passive"))
      (node (ref "R12") (pin "2") (pinfunction "2_2") (pintype "passive"))
      (node (ref "R3") (pin "2") (pinfunction "2_2") (pintype "passive"))
      (node (ref "R4") (pin "2") (pinfunction "2_2") (pintype "passive"))
      (node (ref "R5") (pin "1") (pinfunction "1_1") (pintype "passive"))
      (node (ref "SW1") (pin "3") (pinfunction "S1_3") (pintype "passive"))
      (node (ref "SW1") (pin "4") (pinfunction "S1_4") (pintype "passive"))
      (node (ref "SW2") (pin "3") (pinfunction "S1_3") (pintype "passive"))
      (node (ref "SW2") (pin "4") (pinfunction "S1_4") (pintype "passive"))
      (node (ref "T2") (pin "2") (pinfunction "S_2") (pintype "passive"))
    )
    (net (code "28") (name "Net-(ANT-P)") (class "Default")
      (node (ref "ANT") (pin "1") (pinfunction "P_1") (pintype "passive"))
      (node (ref "IC6") (pin "9") (pinfunction "ANT_9") (pintype "bidirectional"))
    )
    (net (code "29") (name "Net-(D2-PadA)") (class "Default")
      (node (ref "D2") (pin "A") (pinfunction "A_A") (pintype "passive"))
      (node (ref "R7") (pin "2") (pinfunction "2_2") (pintype "passive"))
    )
    (net (code "30") (name "Net-(D4-DI)") (class "Default")
      (node (ref "D4") (pin "4") (pinfunction "DI_4") (pintype "bidirectional"))
      (node (ref "R15") (pin "1") (pinfunction "1_1") (pintype "passive"))
    )
    (net (code "31") (name "Net-(D4-DO)") (class "Default")
      (node (ref "D4") (pin "2") (pinfunction "DO_2") (pintype "bidirectional"))
      (node (ref "D5") (pin "4") (pinfunction "DI_4") (pintype "bidirectional"))
    )
    (net (code "32") (name "Net-(D5-DO)") (class "Default")
      (node (ref "D5") (pin "2") (pinfunction "DO_2") (pintype "bidirectional"))
      (node (ref "D6") (pin "4") (pinfunction "DI_4") (pintype "bidirectional"))
    )
    (net (code "33") (name "Net-(D6-DO)") (class "Default")
      (node (ref "D6") (pin "2") (pinfunction "DO_2") (pintype "bidirectional"))
      (node (ref "D7") (pin "4") (pinfunction "DI_4") (pintype "bidirectional"))
    )
    (net (code "34") (name "Net-(D7-DO)") (class "Default")
      (node (ref "D7") (pin "2") (pinfunction "DO_2") (pintype "bidirectional"))
      (node (ref "J5") (pin "3") (pinfunction "3_3") (pintype "passive"))
    )
    (net (code "35") (name "Net-(F1-Pad1)") (class "Default")
      (node (ref "F1") (pin "1") (pinfunction "1_1") (pintype "passive"))
      (node (ref "J1") (pin "VBUS") (pinfunction "VBUS_VBUS") (pintype "power_in"))
      (node (ref "J1") (pin "VBUS2") (pinfunction "VBUS_VBUS2") (pintype "power_in"))
    )
    (net (code "36") (name "Net-(IC1-VCCANA)") (class "Default")
      (node (ref "C5") (pin "2") (pinfunction "2_2") (pintype "passive"))
      (node (ref "C6") (pin "2") (pinfunction "2_2") (pintype "passive"))
      (node (ref "C7") (pin "2") (pinfunction "2_2") (pintype "passive"))
      (node (ref "IC1") (pin "6") (pinfunction "VCCANA_6") (pintype "power_in"))
      (node (ref "L1") (pin "2") (pinfunction "2_2") (pintype "passive"))
    )
    (net (code "37") (name "Net-(IC1-VCCCORE)") (class "Default")
      (node (ref "C8") (pin "2") (pinfunction "2_2") (pintype "passive"))
      (node (ref "IC1") (pin "43") (pinfunction "VCCCORE_43") (pintype "power_in"))
    )
    (net (code "38") (name "Net-(IC5-~{SDIO}{slash}SPI_CFG)") (class "Default")
      (node (ref "IC5") (pin "10") (pinfunction "~{SDIO}/SPI_CFG_10") (pintype "input"))
      (node (ref "R16") (pin "1") (pinfunction "1_1") (pintype "passive"))
    )
    (net (code "39") (name "Net-(IC6-~{RESET})") (class "Default")
      (node (ref "IC6") (pin "6") (pinfunction "~{RESET}_6") (pintype "input"))
      (node (ref "R17") (pin "1") (pinfunction "1_1") (pintype "passive"))
    )
    (net (code "40") (name "Net-(J1-CC1)") (class "Default")
      (node (ref "J1") (pin "A5") (pinfunction "CC1_A5") (pintype "bidirectional"))
      (node (ref "R4") (pin "1") (pinfunction "1_1") (pintype "passive"))
    )
    (net (code "41") (name "Net-(J1-CC2)") (class "Default")
      (node (ref "J1") (pin "B5") (pinfunction "CC2_B5") (pintype "bidirectional"))
      (node (ref "R3") (pin "1") (pinfunction "1_1") (pintype "passive"))
    )
    (net (code "42") (name "Net-(J1-SHIELD-PadS@1)") (class "Default")
      (node (ref "J1") (pin "S@1") (pinfunction "SHIELD_S@1") (pintype "passive"))
      (node (ref "J1") (pin "S@2") (pinfunction "SHIELD_S@2") (pintype "passive"))
      (node (ref "J1") (pin "S@3") (pinfunction "SHIELD_S@3") (pintype "passive"))
      (node (ref "J1") (pin "S@4") (pinfunction "SHIELD_S@4") (pintype "passive"))
      (node (ref "J1") (pin "S@5") (pinfunction "SHIELD_S@5") (pintype "passive"))
      (node (ref "J1") (pin "S@6") (pinfunction "SHIELD_S@6") (pintype "passive"))
      (node (ref "J1") (pin "S@7") (pinfunction "SHIELD_S@7") (pintype "passive"))
      (node (ref "J1") (pin "S@8") (pinfunction "SHIELD_S@8") (pintype "passive"))
      (node (ref "J1") (pin "S@9") (pinfunction "SHIELD_S@9") (pintype "passive"))
      (node (ref "R5") (pin "2") (pinfunction "2_2") (pintype "passive"))
    )
    (net (code "43") (name "Net-(LS1-N)") (class "Default")
      (node (ref "LS1") (pin "-") (pinfunction "N_-") (pintype "passive"))
      (node (ref "T2") (pin "3") (pinfunction "D_3") (pintype "passive"))
    )
    (net (code "44") (name "Net-(R2-Pad2)") (class "Default")
      (node (ref "R2") (pin "2") (pinfunction "2_2") (pintype "passive"))
      (node (ref "SW1") (pin "1") (pinfunction "P1_1") (pintype "passive"))
      (node (ref "SW1") (pin "2") (pinfunction "P1_2") (pintype "passive"))
    )
    (net (code "45") (name "Net-(T2-G)") (class "Default")
      (node (ref "R11") (pin "2") (pinfunction "2_2") (pintype "passive"))
      (node (ref "R12") (pin "1") (pinfunction "1_1") (pintype "passive"))
      (node (ref "T2") (pin "1") (pinfunction "G_1") (pintype "passive"))
    )
    (net (code "46") (name "RST") (class "Default")
      (node (ref "C1") (pin "2") (pinfunction "2_2") (pintype "passive"))
      (node (ref "IC1") (pin "40") (pinfunction "~{RESET}_40") (pintype "input"))
      (node (ref "J2") (pin "RST") (pinfunction "RST_RST") (pintype "bidirectional"))
      (node (ref "J3") (pin "3-RST") (pinfunction "RST_3-RST") (pintype "bidirectional"))
      (node (ref "R1") (pin "2") (pinfunction "2_2") (pintype "passive"))
      (node (ref "R2") (pin "1") (pinfunction "1_1") (pintype "passive"))
    )
    (net (code "47") (name "SWCLK") (class "Default")
      (node (ref "IC1") (pin "45") (pinfunction "(SWCLK/S1:2/T1:0)PA30_45") (pintype "bidirectional"))
      (node (ref "J2") (pin "SWCLK") (pinfunction "SWCLK_SWCLK") (pintype "bidirectional"))
      (node (ref "J3") (pin "4-SWDCLK") (pinfunction "SWCLK_4-SWDCLK") (pintype "bidirectional"))
      (node (ref "R6") (pin "2") (pinfunction "2_2") (pintype "passive"))
    )
    (net (code "48") (name "SWDIO") (class "Default")
      (node (ref "IC1") (pin "46") (pinfunction "(SWDIO/S1:3/T1:1)PA31_46") (pintype "bidirectional"))
      (node (ref "J2") (pin "SWDIO") (pinfunction "SWDIO_SWDIO") (pintype "bidirectional"))
      (node (ref "J3") (pin "5-SWDIO") (pinfunction "SWDIO_5-SWDIO") (pintype "bidirectional"))
    )
    (net (code "49") (name "USB_N") (class "Default")
      (node (ref "D1") (pin "1") (pinfunction "C1_1") (pintype "passive"))
      (node (ref "IC1") (pin "33") (pinfunction "(USBM/S3:2|5:2/T5:0|1:2)PA24_33") (pintype "bidirectional"))
      (node (ref "J1") (pin "A7") (pinfunction "D-_A7") (pintype "bidirectional"))
      (node (ref "J1") (pin "B7") (pinfunction "D-_B7") (pintype "bidirectional"))
    )
    (net (code "50") (name "USB_P") (class "Default")
      (node (ref "D1") (pin "2") (pinfunction "C2_2") (pintype "passive"))
      (node (ref "IC1") (pin "34") (pinfunction "(USBP/S3:3|5:3/T5:1|1:3)PA25_34") (pintype "bidirectional"))
      (node (ref "J1") (pin "A6") (pinfunction "D+_A6") (pintype "bidirectional"))
      (node (ref "J1") (pin "B6") (pinfunction "D+_B6") (pintype "bidirectional"))
    )
    (net (code "51") (name "unconnected-(IC1-(S0:0{slash}T0:0{slash}REFB{slash}AIN4)PA04-Pad9)") (class "Default")
      (node (ref "IC1") (pin "9") (pinfunction "(S0:0/T0:0/REFB/AIN4)PA04_9") (pintype "bidirectional"))
    )
    (net (code "52") (name "unconnected-(IC1-(S0:2{slash}T1:0{slash}AIN6)PA06-Pad11)") (class "Default")
      (node (ref "IC1") (pin "11") (pinfunction "(S0:2/T1:0/AIN6)PA06_11") (pintype "bidirectional"))
    )
    (net (code "53") (name "unconnected-(IC1-(S0:3{slash}T1:1{slash}AIN7)PA07-Pad12)") (class "Default")
      (node (ref "IC1") (pin "12") (pinfunction "(S0:3/T1:1/AIN7)PA07_12") (pintype "bidirectional"))
    )
    (net (code "54") (name "unconnected-(IC1-(S0:3|2:3{slash}T1:1|0:3{slash}AIN19)PA11-Pad16)") (class "Default")
      (node (ref "IC1") (pin "16") (pinfunction "(S0:3|2:3/T1:1|0:3/AIN19)PA11_16") (pintype "bidirectional"))
    )
    (net (code "55") (name "unconnected-(IC1-(S4:0{slash}T4:0{slash}AIN2)PB08-Pad7)") (class "Default")
      (node (ref "IC1") (pin "7") (pinfunction "(S4:0/T4:0/AIN2)PB08_7") (pintype "bidirectional"))
    )
    (net (code "56") (name "unconnected-(IC1-(S4:1{slash}T4:1{slash}AIN3)PB09-Pad8)") (class "Default")
      (node (ref "IC1") (pin "8") (pinfunction "(S4:1/T4:1/AIN3)PB09_8") (pintype "bidirectional"))
    )
    (net (code "57") (name "unconnected-(IC1-(S5:0{slash}T6:0{slash}AIN10)PB02-Pad47)") (class "Default")
      (node (ref "IC1") (pin "47") (pinfunction "(S5:0/T6:0/AIN10)PB02_47") (pintype "bidirectional"))
    )
    (net (code "58") (name "unconnected-(IC1-(SCL{slash}S3:1|5:1{slash}T4:1|0:5)PA23-Pad32)") (class "Default")
      (node (ref "IC1") (pin "32") (pinfunction "(SCL/S3:1|5:1/T4:1|0:5)PA23_32") (pintype "bidirectional"))
    )
    (net (code "59") (name "unconnected-(IC1-(XIN32{slash}S1:0{slash}T2:0)PA00-Pad1)") (class "Default")
      (node (ref "IC1") (pin "1") (pinfunction "(XIN32/S1:0/T2:0)PA00_1") (pintype "bidirectional"))
    )
    (net (code "60") (name "unconnected-(IC1-(XOUT32{slash}S1:1{slash}T2:1)PA01-Pad2)") (class "Default")
      (node (ref "IC1") (pin "2") (pinfunction "(XOUT32/S1:1/T2:1)PA01_2") (pintype "bidirectional"))
    )
    (net (code "61") (name "unconnected-(IC1-PA28-Pad41)") (class "Default")
      (node (ref "IC1") (pin "41") (pinfunction "PA28_41") (pintype "bidirectional"))
    )
    (net (code "62") (name "unconnected-(IC3A-PWM-Pad6)") (class "Default")
      (node (ref "IC3A") (pin "6") (pinfunction "PWM_6") (pintype "output"))
    )
    (net (code "63") (name "unconnected-(IC3A-RDY-Pad5)") (class "Default")
      (node (ref "IC3A") (pin "5") (pinfunction "RDY_5") (pintype "output"))
    )
    (net (code "64") (name "unconnected-(IC3A-SEL-Pad7)") (class "Default")
      (node (ref "IC3A") (pin "7") (pinfunction "SEL_7") (pintype "bidirectional"))
    )
    (net (code "65") (name "unconnected-(IC5-15{slash}IO4-Pad26)") (class "Default")
      (node (ref "IC5") (pin "26") (pinfunction "15/IO4_26") (pintype "bidirectional"))
    )
    (net (code "66") (name "unconnected-(IC5-16{slash}IO5-Pad27)") (class "Default")
      (node (ref "IC5") (pin "27") (pinfunction "16/IO5_27") (pintype "bidirectional"))
    )
    (net (code "67") (name "unconnected-(IC5-18{slash}IO6-Pad1)") (class "Default")
      (node (ref "IC5") (pin "1") (pinfunction "18/IO6_1") (pintype "bidirectional"))
    )
    (net (code "68") (name "unconnected-(IC5-IO3-Pad25)") (class "Default")
      (node (ref "IC5") (pin "25") (pinfunction "IO3_25") (pintype "bidirectional"))
    )
    (net (code "69") (name "unconnected-(IC5-RTC{slash}IO1-Pad21)") (class "Default")
      (node (ref "IC5") (pin "21") (pinfunction "RTC/IO1_21") (pintype "bidirectional"))
    )
    (net (code "70") (name "unconnected-(IC5-SCL-Pad2)") (class "Default")
      (node (ref "IC5") (pin "2") (pinfunction "SCL_2") (pintype "bidirectional"))
    )
    (net (code "71") (name "unconnected-(IC5-SDA-Pad3)") (class "Default")
      (node (ref "IC5") (pin "3") (pinfunction "SDA_3") (pintype "bidirectional"))
    )
    (net (code "72") (name "unconnected-(IC5-TP_1P3V-Pad24)") (class "Default")
      (node (ref "IC5") (pin "24") (pinfunction "TP_1P3V_24") (pintype "bidirectional"))
    )
    (net (code "73") (name "unconnected-(IC6-DIO2-Pad16)") (class "Default")
      (node (ref "IC6") (pin "16") (pinfunction "DIO2_16") (pintype "bidirectional"))
    )
    (net (code "74") (name "unconnected-(IC6-DIO3-Pad11)") (class "Default")
      (node (ref "IC6") (pin "11") (pinfunction "DIO3_11") (pintype "bidirectional"))
    )
    (net (code "75") (name "unconnected-(IC6-DIO4-Pad12)") (class "Default")
      (node (ref "IC6") (pin "12") (pinfunction "DIO4_12") (pintype "bidirectional"))
    )
    (net (code "76") (name "unconnected-(IC6-DIO5-Pad7)") (class "Default")
      (node (ref "IC6") (pin "7") (pinfunction "DIO5_7") (pintype "bidirectional"))
    )
    (net (code "77") (name "unconnected-(IC7B-INT_DRDY-Pad7)") (class "Default")
      (node (ref "IC7B") (pin "7") (pinfunction "INT_DRDY_7") (pintype "bidirectional"))
    )
    (net (code "78") (name "unconnected-(J5-Pad4)") (class "Default")
      (node (ref "J5") (pin "4") (pinfunction "4_4") (pintype "passive"))
    )
  )
)
